# 6-Accelerometer.net
KiCad netlist of a schematic drawn in Altium Designer
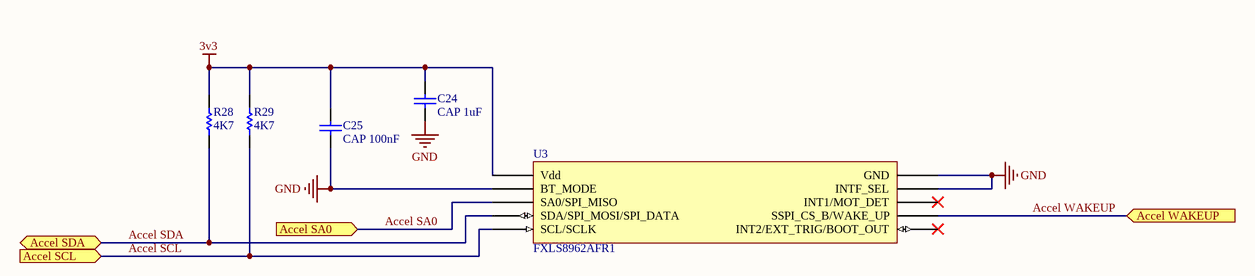
[diagram p0: 6-Accelerometer.SchDoc]

(export (version "E")
  (design (tool "Eeschema 10.0.6"))
  (components
    (comp (ref "C24")
      (value "CAP 1uF")
      (footprint "CAPC0603(1608)100_N")
      (description "CAP 1uF 16V ±5% 0603 (1608 Metric) Thickness 1mm SMD")
      (fields (field (name "TOLERANCE") "Â±5%"))
      (libsource (lib "Altium Content Vault") (part "CAP"))
    )
    (comp (ref "C25")
      (value "CAP 100nF")
      (footprint "CAPC0603(1608)100_N")
      (description "CAP 100nF 25V ±20% 0603 (1608 Metric) Thickness 1mm SMD")
      (fields (field (name "TOLERANCE") "Â±20%"))
      (libsource (lib "Altium Content Vault") (part "CAP"))
    )
    (comp (ref "R28")
      (value "4K7")
      (footprint "RESC0603(1608)_N")
      (fields (field (name "TOLERANCE") "5 %") (field (name "POWER") "0.1 W"))
      (libsource (lib "Altium Content Vault") (part "RES"))
    )
    (comp (ref "R29")
      (value "4K7")
      (footprint "RESC0603(1608)_N")
      (description "4K7 5% 0603(1608)")
      (fields (field (name "TOLERANCE") "5 %") (field (name "POWER") "0.1 W"))
      (libsource (lib "Altium Content Vault") (part "RES"))
    )
    (comp (ref "U3")
      (value "FXLS8962AFR1")
      (footprint "FXLS8962AFR1")
      (description "3 axis accelerometer")
      (libsource (lib "VCB20") (part "FXLS8962AFR1"))
    )
  )
  (nets
    (net (code "1") (name "/Accel SA0") (class "Default")
      (node (ref "U3") (pin "3") (pinfunction "SA0/SPI_MISO_3") (pintype "passive"))
    )
    (net (code "2") (name "/Accel SCL") (class "Default")
      (node (ref "R29") (pin "1") (pinfunction "1_1") (pintype "passive"))
      (node (ref "U3") (pin "5") (pinfunction "SCL/SCLK_5") (pintype "input"))
    )
    (net (code "3") (name "/Accel SDA") (class "Default")
      (node (ref "R28") (pin "1") (pinfunction "1_1") (pintype "passive"))
      (node (ref "U3") (pin "4") (pinfunction "SDA/SPI_MOSI/SPI_DATA_4") (pintype "bidirectional"))
    )
    (net (code "4") (name "/Accel WAKEUP") (class "Default")
      (node (ref "U3") (pin "7") (pinfunction "SSPI_CS_B/WAKE_UP_7") (pintype "passive"))
    )
    (net (code "5") (name "3v3") (class "Default")
      (node (ref "C24") (pin "2") (pinfunction "2_2") (pintype "passive"))
      (node (ref "C25") (pin "2") (pinfunction "2_2") (pintype "passive"))
      (node (ref "R28") (pin "2") (pinfunction "2_2") (pintype "passive"))
      (node (ref "R29") (pin "2") (pinfunction "2_2") (pintype "passive"))
      (node (ref "U3") (pin "1") (pinfunction "Vdd_1") (pintype "power_in"))
    )
    (net (code "6") (name "GND") (class "Default")
      (node (ref "C24") (pin "1") (pinfunction "1_1") (pintype "passive"))
      (node (ref "C25") (pin "1") (pinfunction "1_1") (pintype "passive"))
      (node (ref "U3") (pin "10") (pinfunction "GND_10") (pintype "power_in"))
      (node (ref "U3") (pin "2") (pinfunction "BT_MODE_2") (pintype "passive"))
      (node (ref "U3") (pin "9") (pinfunction "INTF_SEL_9") (pintype "passive"))
    )
    (net (code "7") (name "unconnected-(U3-INT1{slash}MOT_DET-Pad8)") (class "Default")
      (node (ref "U3") (pin "8") (pinfunction "INT1/MOT_DET_8") (pintype "passive+no_connect"))
    )
    (net (code "8") (name "unconnected-(U3-INT2{slash}EXT_TRIG{slash}BOOT_OUT-Pad6)") (class "Default")
      (node (ref "U3") (pin "6") (pinfunction "INT2/EXT_TRIG/BOOT_OUT_6") (pintype "bidirectional+no_connect"))
    )
  )
)
